# Bluepill.net
KiCad netlist of a schematic drawn in Altium Designer
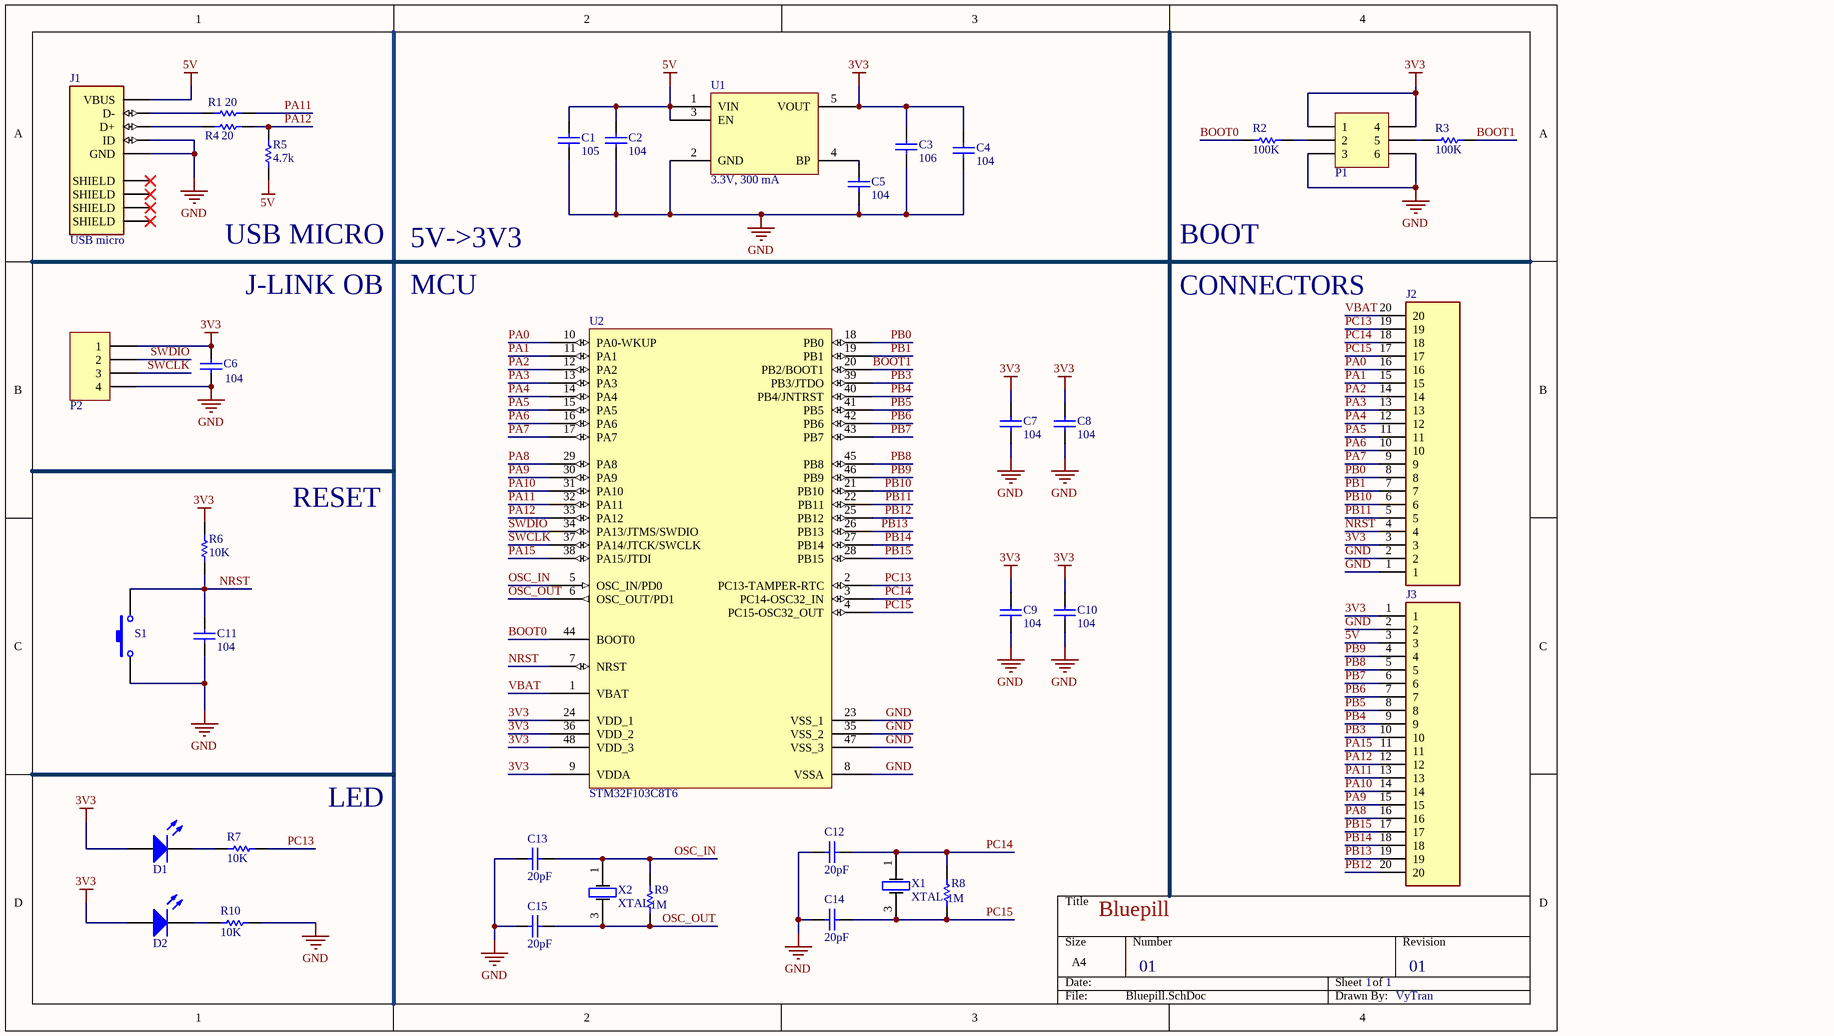
[diagram p0: Bluepill.SchDoc]

(export (version "E")
  (design (tool "Eeschema 10.0.6"))
  (components
    (comp (ref "C1")
      (value "105")
      (footprint "C0805")
      (fields (field (name "Comment") "Capacitor"))
      (libsource (lib "MiclsLib") (part "Capacitor"))
    )
    (comp (ref "C2")
      (value "104")
      (footprint "C0805")
      (fields (field (name "Comment") "Capacitor"))
      (libsource (lib "MiclsLib") (part "Capacitor"))
    )
    (comp (ref "C3")
      (value "106")
      (footprint "C0805")
      (fields (field (name "Comment") "Capacitor"))
      (libsource (lib "MiclsLib") (part "Capacitor"))
    )
    (comp (ref "C4")
      (value "104")
      (footprint "C0805")
      (fields (field (name "Comment") "Capacitor"))
      (libsource (lib "MiclsLib") (part "Capacitor"))
    )
    (comp (ref "C5")
      (value "104")
      (footprint "C0805")
      (fields (field (name "Comment") "Capacitor"))
      (libsource (lib "MiclsLib") (part "Capacitor"))
    )
    (comp (ref "C6")
      (value "104")
      (footprint "C0805")
      (fields (field (name "Comment") "Capacitor"))
      (libsource (lib "MiclsLib") (part "Capacitor"))
    )
    (comp (ref "C7")
      (value "104")
      (footprint "C0805")
      (fields (field (name "Comment") "Capacitor"))
      (libsource (lib "MiclsLib") (part "Capacitor"))
    )
    (comp (ref "C8")
      (value "104")
      (footprint "C0805")
      (fields (field (name "Comment") "Capacitor"))
      (libsource (lib "MiclsLib") (part "Capacitor"))
    )
    (comp (ref "C9")
      (value "104")
      (footprint "C0805")
      (fields (field (name "Comment") "Capacitor"))
      (libsource (lib "MiclsLib") (part "Capacitor"))
    )
    (comp (ref "C10")
      (value "104")
      (footprint "C0805")
      (fields (field (name "Comment") "Capacitor"))
      (libsource (lib "MiclsLib") (part "Capacitor"))
    )
    (comp (ref "C11")
      (value "104")
      (footprint "C0805")
      (fields (field (name "Comment") "Capacitor"))
      (libsource (lib "MiclsLib") (part "Capacitor"))
    )
    (comp (ref "C12")
      (value "20pF")
      (footprint "C0805")
      (fields (field (name "Comment") "Capacitor"))
      (libsource (lib "MiclsLib") (part "Capacitor"))
    )
    (comp (ref "C13")
      (value "20pF")
      (footprint "C0805")
      (fields (field (name "Comment") "Capacitor"))
      (libsource (lib "MiclsLib") (part "Capacitor"))
    )
    (comp (ref "C14")
      (value "20pF")
      (footprint "C0805")
      (fields (field (name "Comment") "Capacitor"))
      (libsource (lib "MiclsLib") (part "Capacitor"))
    )
    (comp (ref "C15")
      (value "20pF")
      (footprint "C0805")
      (fields (field (name "Comment") "Capacitor"))
      (libsource (lib "MiclsLib") (part "Capacitor"))
    )
    (comp (ref "D1")
      (value "LED SMD")
      (footprint "LED_0603_Blue")
      (description "LED")
      (libsource (lib "PIF_Library") (part "LED SMD"))
    )
    (comp (ref "D2")
      (value "LED SMD")
      (footprint "LED_0603_Blue")
      (description "LED")
      (libsource (lib "PIF_Library") (part "LED SMD"))
    )
    (comp (ref "J1")
      (value "USB micro")
      (footprint "GCT_USB3090-XX-X_REVE")
      (fields (field (name "MF") "Global Connector Technology") (field (name "MP") "USB3090-30-A"))
      (libsource (lib "USB3090-XX-X_REVE") (part "USB3090-XX-X_REVE"))
    )
    (comp (ref "J2")
      (value "2-87220-0")
      (footprint "TE_2-87220-0")
      (description "Conn Unshrouded Header HDR 20 POS 2.54mm Solder ST Thru-Hole Carton")
      (fields (field (name "MF") "TE Connectivity"))
      (libsource (lib "") (part "2-87220-0_1"))
    )
    (comp (ref "J3")
      (value "2-87220-0")
      (footprint "TE_2-87220-0")
      (description "Conn Unshrouded Header HDR 20 POS 2.54mm Solder ST Thru-Hole Carton")
      (fields (field (name "MF") "TE Connectivity"))
      (libsource (lib "2-87220-0") (part "2-87220-0"))
    )
    (comp (ref "P1")
      (value "Header 3X2")
      (footprint "JP3x2")
      (description "Header, 3-Pin, Dual row")
      (fields (field (name "PUBLISHER") "Altium Limited"))
      (libsource (lib "PIF_Library") (part "Header 3X2"))
    )
    (comp (ref "P2")
      (value "Header 4")
      (footprint "JP4")
      (description "Header, 4-Pin")
      (fields (field (name "PUBLISHER") "Altium Limited"))
      (libsource (lib "PIF_Library") (part "Header 4"))
    )
    (comp (ref "R1")
      (value "20")
      (footprint "R0805")
      (fields (field (name "Comment") "Resistor"))
      (libsource (lib "MiclsLib") (part "Resistor"))
    )
    (comp (ref "R2")
      (value "100K")
      (footprint "R0805")
      (fields (field (name "Comment") "Resistor"))
      (libsource (lib "MiclsLib") (part "Resistor"))
    )
    (comp (ref "R3")
      (value "100K")
      (footprint "R0805")
      (fields (field (name "Comment") "Resistor"))
      (libsource (lib "MiclsLib") (part "Resistor"))
    )
    (comp (ref "R4")
      (value "20")
      (footprint "R0805")
      (fields (field (name "Comment") "Resistor"))
      (libsource (lib "MiclsLib") (part "Resistor"))
    )
    (comp (ref "R5")
      (value "4.7k")
      (footprint "R0805")
      (fields (field (name "Comment") "Resistor"))
      (libsource (lib "MiclsLib") (part "Resistor"))
    )
    (comp (ref "R6")
      (value "10K")
      (footprint "R0805")
      (fields (field (name "Comment") "Resistor"))
      (libsource (lib "MiclsLib") (part "Resistor"))
    )
    (comp (ref "R7")
      (value "10K")
      (footprint "R0805")
      (fields (field (name "Comment") "Resistor"))
      (libsource (lib "MiclsLib") (part "Resistor"))
    )
    (comp (ref "R8")
      (value "1M")
      (footprint "R0805")
      (fields (field (name "Comment") "Resistor"))
      (libsource (lib "MiclsLib") (part "Resistor"))
    )
    (comp (ref "R9")
      (value "1M")
      (footprint "R0805")
      (fields (field (name "Comment") "Resistor"))
      (libsource (lib "MiclsLib") (part "Resistor"))
    )
    (comp (ref "R10")
      (value "10K")
      (footprint "R0805")
      (fields (field (name "Comment") "Resistor"))
      (libsource (lib "MiclsLib") (part "Resistor"))
    )
    (comp (ref "S1")
      (value "Tact SW - 2Pin")
      (footprint "SW-SMD")
      (description "Switch button 2 pin")
      (libsource (lib "PIF_Library") (part "Tact SW - 2Pin"))
    )
    (comp (ref "U1")
      (value "3.3V, 300 mA")
      (footprint "RT9193-xxGB")
      (description "LDO Voltage Regulators 300mA, Ultra-Low Noise, Ultra-Fast CMOS LDO Regulator, SOT-23-5,  3.3 V")
      (fields (field (name "MANUFACTURER") "Richtek"))
      (libsource (lib "Altium_Power_Supply_IC") (part "RT9193-33GB"))
    )
    (comp (ref "U2")
      (value "STM32F103C8T6")
      (footprint "TSQFP50P900X900X160-48N")
      (fields (field (name "MANUFACTURER") "ST"))
      (libsource (lib "MiclsLib") (part "STM32F103C8T6"))
    )
    (comp (ref "X1") (value "XTAL") (footprint "XTAL 3225") (libsource (lib "MiclsLib") (part "XTAL")))
    (comp (ref "X2") (value "XTAL") (footprint "XTAL 3225") (libsource (lib "MiclsLib") (part "XTAL")))
  )
  (nets
    (net (code "1") (name "/BOOT0") (class "Default")
      (node (ref "R2") (pin "2") (pinfunction "2_2") (pintype "passive"))
      (node (ref "U2") (pin "44") (pinfunction "BOOT0_44") (pintype "passive"))
    )
    (net (code "2") (name "/BOOT1") (class "Default")
      (node (ref "R3") (pin "1") (pinfunction "1_1") (pintype "passive"))
      (node (ref "U2") (pin "20") (pinfunction "PB2/BOOT1_20") (pintype "bidirectional"))
    )
    (net (code "3") (name "/NRST") (class "Default")
      (node (ref "C11") (pin "2") (pinfunction "2_2") (pintype "passive"))
      (node (ref "J2") (pin "4") (pinfunction "4_4") (pintype "passive"))
      (node (ref "R6") (pin "1") (pinfunction "1_1") (pintype "passive"))
      (node (ref "S1") (pin "2") (pinfunction "2_2") (pintype "passive"))
      (node (ref "U2") (pin "7") (pinfunction "NRST_7") (pintype "bidirectional"))
    )
    (net (code "4") (name "/OSC_IN") (class "Default")
      (node (ref "C13") (pin "1") (pinfunction "1_1") (pintype "passive"))
      (node (ref "R9") (pin "2") (pinfunction "2_2") (pintype "passive"))
      (node (ref "U2") (pin "5") (pinfunction "OSC_IN/PD0_5") (pintype "input"))
      (node (ref "X2") (pin "1") (pinfunction "8_1") (pintype "passive"))
    )
    (net (code "5") (name "/OSC_OUT") (class "Default")
      (node (ref "C15") (pin "1") (pinfunction "1_1") (pintype "passive"))
      (node (ref "R9") (pin "1") (pinfunction "1_1") (pintype "passive"))
      (node (ref "U2") (pin "6") (pinfunction "OSC_OUT/PD1_6") (pintype "output"))
      (node (ref "X2") (pin "3") (pinfunction "9_3") (pintype "passive"))
    )
    (net (code "6") (name "/PA0") (class "Default")
      (node (ref "J2") (pin "16") (pinfunction "16_16") (pintype "passive"))
      (node (ref "U2") (pin "10") (pinfunction "PA0-WKUP_10") (pintype "bidirectional"))
    )
    (net (code "7") (name "/PA1") (class "Default")
      (node (ref "J2") (pin "15") (pinfunction "15_15") (pintype "passive"))
      (node (ref "U2") (pin "11") (pinfunction "PA1_11") (pintype "bidirectional"))
    )
    (net (code "8") (name "/PA2") (class "Default")
      (node (ref "J2") (pin "14") (pinfunction "14_14") (pintype "passive"))
      (node (ref "U2") (pin "12") (pinfunction "PA2_12") (pintype "bidirectional"))
    )
    (net (code "9") (name "/PA3") (class "Default")
      (node (ref "J2") (pin "13") (pinfunction "13_13") (pintype "passive"))
      (node (ref "U2") (pin "13") (pinfunction "PA3_13") (pintype "bidirectional"))
    )
    (net (code "10") (name "/PA4") (class "Default")
      (node (ref "J2") (pin "12") (pinfunction "12_12") (pintype "passive"))
      (node (ref "U2") (pin "14") (pinfunction "PA4_14") (pintype "bidirectional"))
    )
    (net (code "11") (name "/PA5") (class "Default")
      (node (ref "J2") (pin "11") (pinfunction "11_11") (pintype "passive"))
      (node (ref "U2") (pin "15") (pinfunction "PA5_15") (pintype "bidirectional"))
    )
    (net (code "12") (name "/PA6") (class "Default")
      (node (ref "J2") (pin "10") (pinfunction "10_10") (pintype "passive"))
      (node (ref "U2") (pin "16") (pinfunction "PA6_16") (pintype "bidirectional"))
    )
    (net (code "13") (name "/PA7") (class "Default")
      (node (ref "J2") (pin "9") (pinfunction "9_9") (pintype "passive"))
      (node (ref "U2") (pin "17") (pinfunction "PA7_17") (pintype "bidirectional"))
    )
    (net (code "14") (name "/PA8") (class "Default")
      (node (ref "J3") (pin "16") (pinfunction "16_16") (pintype "passive"))
      (node (ref "U2") (pin "29") (pinfunction "PA8_29") (pintype "bidirectional"))
    )
    (net (code "15") (name "/PA9") (class "Default")
      (node (ref "J3") (pin "15") (pinfunction "15_15") (pintype "passive"))
      (node (ref "U2") (pin "30") (pinfunction "PA9_30") (pintype "bidirectional"))
    )
    (net (code "16") (name "/PA10") (class "Default")
      (node (ref "J3") (pin "14") (pinfunction "14_14") (pintype "passive"))
      (node (ref "U2") (pin "31") (pinfunction "PA10_31") (pintype "bidirectional"))
    )
    (net (code "17") (name "/PA11") (class "Default")
      (node (ref "J3") (pin "13") (pinfunction "13_13") (pintype "passive"))
      (node (ref "R1") (pin "1") (pinfunction "1_1") (pintype "passive"))
      (node (ref "U2") (pin "32") (pinfunction "PA11_32") (pintype "bidirectional"))
    )
    (net (code "18") (name "/PA12") (class "Default")
      (node (ref "J3") (pin "12") (pinfunction "12_12") (pintype "passive"))
      (node (ref "R4") (pin "1") (pinfunction "1_1") (pintype "passive"))
      (node (ref "R5") (pin "2") (pinfunction "2_2") (pintype "passive"))
      (node (ref "U2") (pin "33") (pinfunction "PA12_33") (pintype "bidirectional"))
    )
    (net (code "19") (name "/PA15") (class "Default")
      (node (ref "J3") (pin "11") (pinfunction "11_11") (pintype "passive"))
      (node (ref "U2") (pin "38") (pinfunction "PA15/JTDI_38") (pintype "bidirectional"))
    )
    (net (code "20") (name "/PB0") (class "Default")
      (node (ref "J2") (pin "8") (pinfunction "8_8") (pintype "passive"))
      (node (ref "U2") (pin "18") (pinfunction "PB0_18") (pintype "bidirectional"))
    )
    (net (code "21") (name "/PB1") (class "Default")
      (node (ref "J2") (pin "7") (pinfunction "7_7") (pintype "passive"))
      (node (ref "U2") (pin "19") (pinfunction "PB1_19") (pintype "bidirectional"))
    )
    (net (code "22") (name "/PB3") (class "Default")
      (node (ref "J3") (pin "10") (pinfunction "10_10") (pintype "passive"))
      (node (ref "U2") (pin "39") (pinfunction "PB3/JTDO_39") (pintype "bidirectional"))
    )
    (net (code "23") (name "/PB4") (class "Default")
      (node (ref "J3") (pin "9") (pinfunction "9_9") (pintype "passive"))
      (node (ref "U2") (pin "40") (pinfunction "PB4/JNTRST_40") (pintype "bidirectional"))
    )
    (net (code "24") (name "/PB5") (class "Default")
      (node (ref "J3") (pin "8") (pinfunction "8_8") (pintype "passive"))
      (node (ref "U2") (pin "41") (pinfunction "PB5_41") (pintype "bidirectional"))
    )
    (net (code "25") (name "/PB6") (class "Default")
      (node (ref "J3") (pin "7") (pinfunction "7_7") (pintype "passive"))
      (node (ref "U2") (pin "42") (pinfunction "PB6_42") (pintype "bidirectional"))
    )
    (net (code "26") (name "/PB7") (class "Default")
      (node (ref "J3") (pin "6") (pinfunction "6_6") (pintype "passive"))
      (node (ref "U2") (pin "43") (pinfunction "PB7_43") (pintype "bidirectional"))
    )
    (net (code "27") (name "/PB8") (class "Default")
      (node (ref "J3") (pin "5") (pinfunction "5_5") (pintype "passive"))
      (node (ref "U2") (pin "45") (pinfunction "PB8_45") (pintype "bidirectional"))
    )
    (net (code "28") (name "/PB9") (class "Default")
      (node (ref "J3") (pin "4") (pinfunction "4_4") (pintype "passive"))
      (node (ref "U2") (pin "46") (pinfunction "PB9_46") (pintype "bidirectional"))
    )
    (net (code "29") (name "/PB10") (class "Default")
      (node (ref "J2") (pin "6") (pinfunction "6_6") (pintype "passive"))
      (node (ref "U2") (pin "21") (pinfunction "PB10_21") (pintype "bidirectional"))
    )
    (net (code "30") (name "/PB11") (class "Default")
      (node (ref "J2") (pin "5") (pinfunction "5_5") (pintype "passive"))
      (node (ref "U2") (pin "22") (pinfunction "PB11_22") (pintype "bidirectional"))
    )
    (net (code "31") (name "/PB12") (class "Default")
      (node (ref "J3") (pin "20") (pinfunction "20_20") (pintype "passive"))
      (node (ref "U2") (pin "25") (pinfunction "PB12_25") (pintype "bidirectional"))
    )
    (net (code "32") (name "/PB13") (class "Default")
      (node (ref "J3") (pin "19") (pinfunction "19_19") (pintype "passive"))
      (node (ref "U2") (pin "26") (pinfunction "PB13_26") (pintype "bidirectional"))
    )
    (net (code "33") (name "/PB14") (class "Default")
      (node (ref "J3") (pin "18") (pinfunction "18_18") (pintype "passive"))
      (node (ref "U2") (pin "27") (pinfunction "PB14_27") (pintype "bidirectional"))
    )
    (net (code "34") (name "/PB15") (class "Default")
      (node (ref "J3") (pin "17") (pinfunction "17_17") (pintype "passive"))
      (node (ref "U2") (pin "28") (pinfunction "PB15_28") (pintype "bidirectional"))
    )
    (net (code "35") (name "/PC13") (class "Default")
      (node (ref "J2") (pin "19") (pinfunction "19_19") (pintype "passive"))
      (node (ref "R7") (pin "1") (pinfunction "1_1") (pintype "passive"))
      (node (ref "U2") (pin "2") (pinfunction "PC13-TAMPER-RTC_2") (pintype "bidirectional"))
    )
    (net (code "36") (name "/PC14") (class "Default")
      (node (ref "C12") (pin "1") (pinfunction "1_1") (pintype "passive"))
      (node (ref "J2") (pin "18") (pinfunction "18_18") (pintype "passive"))
      (node (ref "R8") (pin "2") (pinfunction "2_2") (pintype "passive"))
      (node (ref "U2") (pin "3") (pinfunction "PC14-OSC32_IN_3") (pintype "bidirectional"))
      (node (ref "X1") (pin "1") (pinfunction "8_1") (pintype "passive"))
    )
    (net (code "37") (name "/PC15") (class "Default")
      (node (ref "C14") (pin "1") (pinfunction "1_1") (pintype "passive"))
      (node (ref "J2") (pin "17") (pinfunction "17_17") (pintype "passive"))
      (node (ref "R8") (pin "1") (pinfunction "1_1") (pintype "passive"))
      (node (ref "U2") (pin "4") (pinfunction "PC15-OSC32_OUT_4") (pintype "bidirectional"))
      (node (ref "X1") (pin "3") (pinfunction "9_3") (pintype "passive"))
    )
    (net (code "38") (name "/SWCLK") (class "Default")
      (node (ref "P2") (pin "3") (pinfunction "3_3") (pintype "passive"))
      (node (ref "U2") (pin "37") (pinfunction "PA14/JTCK/SWCLK_37") (pintype "bidirectional"))
    )
    (net (code "39") (name "/SWDIO") (class "Default")
      (node (ref "P2") (pin "2") (pinfunction "2_2") (pintype "passive"))
      (node (ref "U2") (pin "34") (pinfunction "PA13/JTMS/SWDIO_34") (pintype "bidirectional"))
    )
    (net (code "40") (name "/VBAT") (class "Default")
      (node (ref "J2") (pin "20") (pinfunction "20_20") (pintype "passive"))
      (node (ref "U2") (pin "1") (pinfunction "VBAT_1") (pintype "power_in"))
    )
    (net (code "41") (name "3V3") (class "Default")
      (node (ref "C10") (pin "2") (pinfunction "2_2") (pintype "passive"))
      (node (ref "C3") (pin "2") (pinfunction "2_2") (pintype "passive"))
      (node (ref "C4") (pin "2") (pinfunction "2_2") (pintype "passive"))
      (node (ref "C6") (pin "2") (pinfunction "2_2") (pintype "passive"))
      (node (ref "C7") (pin "2") (pinfunction "2_2") (pintype "passive"))
      (node (ref "C8") (pin "2") (pinfunction "2_2") (pintype "passive"))
      (node (ref "C9") (pin "2") (pinfunction "2_2") (pintype "passive"))
      (node (ref "D1") (pin "1") (pinfunction "A_1") (pintype "passive"))
      (node (ref "D2") (pin "1") (pinfunction "A_1") (pintype "passive"))
      (node (ref "J2") (pin "3") (pinfunction "3_3") (pintype "passive"))
      (node (ref "J3") (pin "1") (pinfunction "1_1") (pintype "passive"))
      (node (ref "P1") (pin "1") (pinfunction "1_1") (pintype "passive"))
      (node (ref "P1") (pin "4") (pinfunction "4_4") (pintype "passive"))
      (node (ref "P2") (pin "1") (pinfunction "1_1") (pintype "passive"))
      (node (ref "R6") (pin "2") (pinfunction "2_2") (pintype "passive"))
      (node (ref "U1") (pin "5") (pinfunction "VOUT_5") (pintype "power_in"))
      (node (ref "U2") (pin "24") (pinfunction "VDD_1_24") (pintype "power_in"))
      (node (ref "U2") (pin "36") (pinfunction "VDD_2_36") (pintype "power_in"))
      (node (ref "U2") (pin "48") (pinfunction "VDD_3_48") (pintype "power_in"))
      (node (ref "U2") (pin "9") (pinfunction "VDDA_9") (pintype "power_in"))
    )
    (net (code "42") (name "5V") (class "Default")
      (node (ref "C1") (pin "2") (pinfunction "2_2") (pintype "passive"))
      (node (ref "C2") (pin "2") (pinfunction "2_2") (pintype "passive"))
      (node (ref "J1") (pin "1") (pinfunction "VBUS_1") (pintype "power_in"))
      (node (ref "J3") (pin "3") (pinfunction "3_3") (pintype "passive"))
      (node (ref "R5") (pin "1") (pinfunction "1_1") (pintype "passive"))
      (node (ref "U1") (pin "1") (pinfunction "VIN_1") (pintype "power_in"))
      (node (ref "U1") (pin "3") (pinfunction "EN_3") (pintype "power_in"))
    )
    (net (code "43") (name "GND") (class "Default")
      (node (ref "C1") (pin "1") (pinfunction "1_1") (pintype "passive"))
      (node (ref "C10") (pin "1") (pinfunction "1_1") (pintype "passive"))
      (node (ref "C11") (pin "1") (pinfunction "1_1") (pintype "passive"))
      (node (ref "C12") (pin "2") (pinfunction "2_2") (pintype "passive"))
      (node (ref "C13") (pin "2") (pinfunction "2_2") (pintype "passive"))
      (node (ref "C14") (pin "2") (pinfunction "2_2") (pintype "passive"))
      (node (ref "C15") (pin "2") (pinfunction "2_2") (pintype "passive"))
      (node (ref "C2") (pin "1") (pinfunction "1_1") (pintype "passive"))
      (node (ref "C3") (pin "1") (pinfunction "1_1") (pintype "passive"))
      (node (ref "C4") (pin "1") (pinfunction "1_1") (pintype "passive"))
      (node (ref "C5") (pin "1") (pinfunction "1_1") (pintype "passive"))
      (node (ref "C6") (pin "1") (pinfunction "1_1") (pintype "passive"))
      (node (ref "C7") (pin "1") (pinfunction "1_1") (pintype "passive"))
      (node (ref "C8") (pin "1") (pinfunction "1_1") (pintype "passive"))
      (node (ref "C9") (pin "1") (pinfunction "1_1") (pintype "passive"))
      (node (ref "J1") (pin "4") (pinfunction "ID_4") (pintype "bidirectional"))
      (node (ref "J1") (pin "5") (pinfunction "GND_5") (pintype "power_in"))
      (node (ref "J2") (pin "1") (pinfunction "1_1") (pintype "passive"))
      (node (ref "J2") (pin "2") (pinfunction "2_2") (pintype "passive"))
      (node (ref "J3") (pin "2") (pinfunction "2_2") (pintype "passive"))
      (node (ref "P1") (pin "3") (pinfunction "3_3") (pintype "passive"))
      (node (ref "P1") (pin "6") (pinfunction "6_6") (pintype "passive"))
      (node (ref "P2") (pin "4") (pinfunction "4_4") (pintype "passive"))
      (node (ref "R10") (pin "1") (pinfunction "1_1") (pintype "passive"))
      (node (ref "S1") (pin "1") (pinfunction "1_1") (pintype "passive"))
      (node (ref "U1") (pin "2") (pinfunction "GND_2") (pintype "power_in"))
      (node (ref "U2") (pin "23") (pinfunction "VSS_1_23") (pintype "power_in"))
      (node (ref "U2") (pin "35") (pinfunction "VSS_2_35") (pintype "power_in"))
      (node (ref "U2") (pin "47") (pinfunction "VSS_3_47") (pintype "power_in"))
      (node (ref "U2") (pin "8") (pinfunction "VSSA_8") (pintype "power_in"))
    )
    (net (code "44") (name "Net-(D1-K)") (class "Default")
      (node (ref "D1") (pin "2") (pinfunction "K_2") (pintype "passive"))
      (node (ref "R7") (pin "2") (pinfunction "2_2") (pintype "passive"))
    )
    (net (code "45") (name "Net-(D2-K)") (class "Default")
      (node (ref "D2") (pin "2") (pinfunction "K_2") (pintype "passive"))
      (node (ref "R10") (pin "2") (pinfunction "2_2") (pintype "passive"))
    )
    (net (code "46") (name "Net-(J1-D+)") (class "Default")
      (node (ref "J1") (pin "3") (pinfunction "D+_3") (pintype "bidirectional"))
      (node (ref "R4") (pin "2") (pinfunction "2_2") (pintype "passive"))
    )
    (net (code "47") (name "Net-(J1-D-)") (class "Default")
      (node (ref "J1") (pin "2") (pinfunction "D-_2") (pintype "bidirectional"))
      (node (ref "R1") (pin "2") (pinfunction "2_2") (pintype "passive"))
    )
    (net (code "48") (name "Net-(P1-Pad2)") (class "Default")
      (node (ref "P1") (pin "2") (pinfunction "2_2") (pintype "passive"))
      (node (ref "R2") (pin "1") (pinfunction "1_1") (pintype "passive"))
    )
    (net (code "49") (name "Net-(P1-Pad5)") (class "Default")
      (node (ref "P1") (pin "5") (pinfunction "5_5") (pintype "passive"))
      (node (ref "R3") (pin "2") (pinfunction "2_2") (pintype "passive"))
    )
    (net (code "50") (name "Net-(U1-BP)") (class "Default")
      (node (ref "C5") (pin "2") (pinfunction "2_2") (pintype "passive"))
      (node (ref "U1") (pin "4") (pinfunction "BP_4") (pintype "power_in"))
    )
    (net (code "51") (name "unconnected-(J1-SHIELD-Pad6)") (class "Default")
      (node (ref "J1") (pin "6") (pinfunction "SHIELD_6") (pintype "power_in+no_connect"))
    )
    (net (code "52") (name "unconnected-(J1-SHIELD-Pad7)") (class "Default")
      (node (ref "J1") (pin "7") (pinfunction "SHIELD_7") (pintype "power_in+no_connect"))
    )
    (net (code "53") (name "unconnected-(J1-SHIELD-Pad8)") (class "Default")
      (node (ref "J1") (pin "8") (pinfunction "SHIELD_8") (pintype "power_in+no_connect"))
    )
    (net (code "54") (name "unconnected-(J1-SHIELD-Pad9)") (class "Default")
      (node (ref "J1") (pin "9") (pinfunction "SHIELD_9") (pintype "power_in+no_connect"))
    )
  )
)
